# fpc-40-breakout.net
KiCad netlist of a schematic drawn in EAGLE
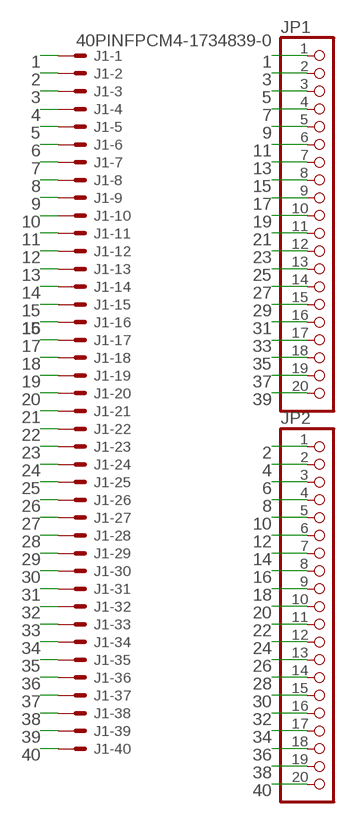
[diagram p0: schematic, sheet 1]

(export (version "E")
  (design (tool "Eeschema 10.0.6"))
  (components
    (comp (ref "J1")
      (value "40PINFPCM4-1734839-0")
      (footprint "eagle-import:4-1734839-0")
      (libsource (lib "eagle-import") (part "40PINFPC4-1734839-0M"))
    )
    (comp (ref "JP1")
      (value "PINHD-1X20/90")
      (footprint "eagle-import:1X20_90")
      (libsource (lib "eagle-import") (part "PINHD-1X20/90"))
    )
    (comp (ref "JP2")
      (value "PINHD-1X20/90")
      (footprint "eagle-import:1X20_90")
      (libsource (lib "eagle-import") (part "PINHD-1X20/90"))
    )
  )
  (nets
    (net (code "1") (name "/1") (class "Default")
      (node (ref "J1") (pin "1") (pinfunction "MSV_1") (pintype "passive"))
      (node (ref "JP1") (pin "1") (pinfunction "1_1") (pintype "passive"))
    )
    (net (code "2") (name "/2") (class "Default")
      (node (ref "J1") (pin "2") (pinfunction "MS_2") (pintype "passive"))
      (node (ref "JP2") (pin "1") (pinfunction "1_1") (pintype "passive"))
    )
    (net (code "3") (name "/3") (class "Default")
      (node (ref "J1") (pin "3") (pinfunction "MS_3") (pintype "passive"))
      (node (ref "JP1") (pin "2") (pinfunction "2_2") (pintype "passive"))
    )
    (net (code "4") (name "/4") (class "Default")
      (node (ref "J1") (pin "4") (pinfunction "MS_4") (pintype "passive"))
      (node (ref "JP2") (pin "2") (pinfunction "2_2") (pintype "passive"))
    )
    (net (code "5") (name "/5") (class "Default")
      (node (ref "J1") (pin "5") (pinfunction "MS_5") (pintype "passive"))
      (node (ref "JP1") (pin "3") (pinfunction "3_3") (pintype "passive"))
    )
    (net (code "6") (name "/6") (class "Default")
      (node (ref "J1") (pin "6") (pinfunction "MS_6") (pintype "passive"))
      (node (ref "JP2") (pin "3") (pinfunction "3_3") (pintype "passive"))
    )
    (net (code "7") (name "/7") (class "Default")
      (node (ref "J1") (pin "7") (pinfunction "MS_7") (pintype "passive"))
      (node (ref "JP1") (pin "4") (pinfunction "4_4") (pintype "passive"))
    )
    (net (code "8") (name "/8") (class "Default")
      (node (ref "J1") (pin "8") (pinfunction "MS_8") (pintype "passive"))
      (node (ref "JP2") (pin "4") (pinfunction "4_4") (pintype "passive"))
    )
    (net (code "9") (name "/9") (class "Default")
      (node (ref "J1") (pin "9") (pinfunction "MS_9") (pintype "passive"))
      (node (ref "JP1") (pin "5") (pinfunction "5_5") (pintype "passive"))
    )
    (net (code "10") (name "/10") (class "Default")
      (node (ref "J1") (pin "10") (pinfunction "MS_10") (pintype "passive"))
      (node (ref "JP2") (pin "5") (pinfunction "5_5") (pintype "passive"))
    )
    (net (code "11") (name "/11") (class "Default")
      (node (ref "J1") (pin "11") (pinfunction "MS_11") (pintype "passive"))
      (node (ref "JP1") (pin "6") (pinfunction "6_6") (pintype "passive"))
    )
    (net (code "12") (name "/12") (class "Default")
      (node (ref "J1") (pin "12") (pinfunction "MS_12") (pintype "passive"))
      (node (ref "JP2") (pin "6") (pinfunction "6_6") (pintype "passive"))
    )
    (net (code "13") (name "/13") (class "Default")
      (node (ref "J1") (pin "13") (pinfunction "MS_13") (pintype "passive"))
      (node (ref "JP1") (pin "7") (pinfunction "7_7") (pintype "passive"))
    )
    (net (code "14") (name "/14") (class "Default")
      (node (ref "J1") (pin "14") (pinfunction "MS_14") (pintype "passive"))
      (node (ref "JP2") (pin "7") (pinfunction "7_7") (pintype "passive"))
    )
    (net (code "15") (name "/15") (class "Default")
      (node (ref "J1") (pin "15") (pinfunction "MS_15") (pintype "passive"))
      (node (ref "JP1") (pin "8") (pinfunction "8_8") (pintype "passive"))
    )
    (net (code "16") (name "/16") (class "Default")
      (node (ref "J1") (pin "16") (pinfunction "MS_16") (pintype "passive"))
      (node (ref "JP2") (pin "8") (pinfunction "8_8") (pintype "passive"))
    )
    (net (code "17") (name "/17") (class "Default")
      (node (ref "J1") (pin "17") (pinfunction "MS_17") (pintype "passive"))
      (node (ref "JP1") (pin "9") (pinfunction "9_9") (pintype "passive"))
    )
    (net (code "18") (name "/18") (class "Default")
      (node (ref "J1") (pin "18") (pinfunction "MS_18") (pintype "passive"))
      (node (ref "JP2") (pin "9") (pinfunction "9_9") (pintype "passive"))
    )
    (net (code "19") (name "/19") (class "Default")
      (node (ref "J1") (pin "19") (pinfunction "MS_19") (pintype "passive"))
      (node (ref "JP1") (pin "10") (pinfunction "10_10") (pintype "passive"))
    )
    (net (code "20") (name "/20") (class "Default")
      (node (ref "J1") (pin "20") (pinfunction "MS_20") (pintype "passive"))
      (node (ref "JP2") (pin "10") (pinfunction "10_10") (pintype "passive"))
    )
    (net (code "21") (name "/21") (class "Default")
      (node (ref "J1") (pin "21") (pinfunction "MS_21") (pintype "passive"))
      (node (ref "JP1") (pin "11") (pinfunction "11_11") (pintype "passive"))
    )
    (net (code "22") (name "/22") (class "Default")
      (node (ref "J1") (pin "22") (pinfunction "MS_22") (pintype "passive"))
      (node (ref "JP2") (pin "11") (pinfunction "11_11") (pintype "passive"))
    )
    (net (code "23") (name "/23") (class "Default")
      (node (ref "J1") (pin "23") (pinfunction "MS_23") (pintype "passive"))
      (node (ref "JP1") (pin "12") (pinfunction "12_12") (pintype "passive"))
    )
    (net (code "24") (name "/24") (class "Default")
      (node (ref "J1") (pin "24") (pinfunction "MS_24") (pintype "passive"))
      (node (ref "JP2") (pin "12") (pinfunction "12_12") (pintype "passive"))
    )
    (net (code "25") (name "/25") (class "Default")
      (node (ref "J1") (pin "25") (pinfunction "MS_25") (pintype "passive"))
      (node (ref "JP1") (pin "13") (pinfunction "13_13") (pintype "passive"))
    )
    (net (code "26") (name "/26") (class "Default")
      (node (ref "J1") (pin "26") (pinfunction "MS_26") (pintype "passive"))
      (node (ref "JP2") (pin "13") (pinfunction "13_13") (pintype "passive"))
    )
    (net (code "27") (name "/27") (class "Default")
      (node (ref "J1") (pin "27") (pinfunction "MS_27") (pintype "passive"))
      (node (ref "JP1") (pin "14") (pinfunction "14_14") (pintype "passive"))
    )
    (net (code "28") (name "/28") (class "Default")
      (node (ref "J1") (pin "28") (pinfunction "MS_28") (pintype "passive"))
      (node (ref "JP2") (pin "14") (pinfunction "14_14") (pintype "passive"))
    )
    (net (code "29") (name "/29") (class "Default")
      (node (ref "J1") (pin "29") (pinfunction "MS_29") (pintype "passive"))
      (node (ref "JP1") (pin "15") (pinfunction "15_15") (pintype "passive"))
    )
    (net (code "30") (name "/30") (class "Default")
      (node (ref "J1") (pin "30") (pinfunction "MS_30") (pintype "passive"))
      (node (ref "JP2") (pin "15") (pinfunction "15_15") (pintype "passive"))
    )
    (net (code "31") (name "/31") (class "Default")
      (node (ref "J1") (pin "31") (pinfunction "MS_31") (pintype "passive"))
      (node (ref "JP1") (pin "16") (pinfunction "16_16") (pintype "passive"))
    )
    (net (code "32") (name "/32") (class "Default")
      (node (ref "J1") (pin "32") (pinfunction "MS_32") (pintype "passive"))
      (node (ref "JP2") (pin "16") (pinfunction "16_16") (pintype "passive"))
    )
    (net (code "33") (name "/33") (class "Default")
      (node (ref "J1") (pin "33") (pinfunction "MS_33") (pintype "passive"))
      (node (ref "JP1") (pin "17") (pinfunction "17_17") (pintype "passive"))
    )
    (net (code "34") (name "/34") (class "Default")
      (node (ref "J1") (pin "34") (pinfunction "MS_34") (pintype "passive"))
      (node (ref "JP2") (pin "17") (pinfunction "17_17") (pintype "passive"))
    )
    (net (code "35") (name "/35") (class "Default")
      (node (ref "J1") (pin "35") (pinfunction "MS_35") (pintype "passive"))
      (node (ref "JP1") (pin "18") (pinfunction "18_18") (pintype "passive"))
    )
    (net (code "36") (name "/36") (class "Default")
      (node (ref "J1") (pin "36") (pinfunction "MS_36") (pintype "passive"))
      (node (ref "JP2") (pin "18") (pinfunction "18_18") (pintype "passive"))
    )
    (net (code "37") (name "/37") (class "Default")
      (node (ref "J1") (pin "37") (pinfunction "MS_37") (pintype "passive"))
      (node (ref "JP1") (pin "19") (pinfunction "19_19") (pintype "passive"))
    )
    (net (code "38") (name "/38") (class "Default")
      (node (ref "J1") (pin "38") (pinfunction "MS_38") (pintype "passive"))
      (node (ref "JP2") (pin "19") (pinfunction "19_19") (pintype "passive"))
    )
    (net (code "39") (name "/39") (class "Default")
      (node (ref "J1") (pin "39") (pinfunction "MS_39") (pintype "passive"))
      (node (ref "JP1") (pin "20") (pinfunction "20_20") (pintype "passive"))
    )
    (net (code "40") (name "/40") (class "Default")
      (node (ref "J1") (pin "40") (pinfunction "MS_40") (pintype "passive"))
      (node (ref "JP2") (pin "20") (pinfunction "20_20") (pintype "passive"))
    )
  )
)
